# final_project.net
KiCad netlist of a schematic drawn in Altium Designer
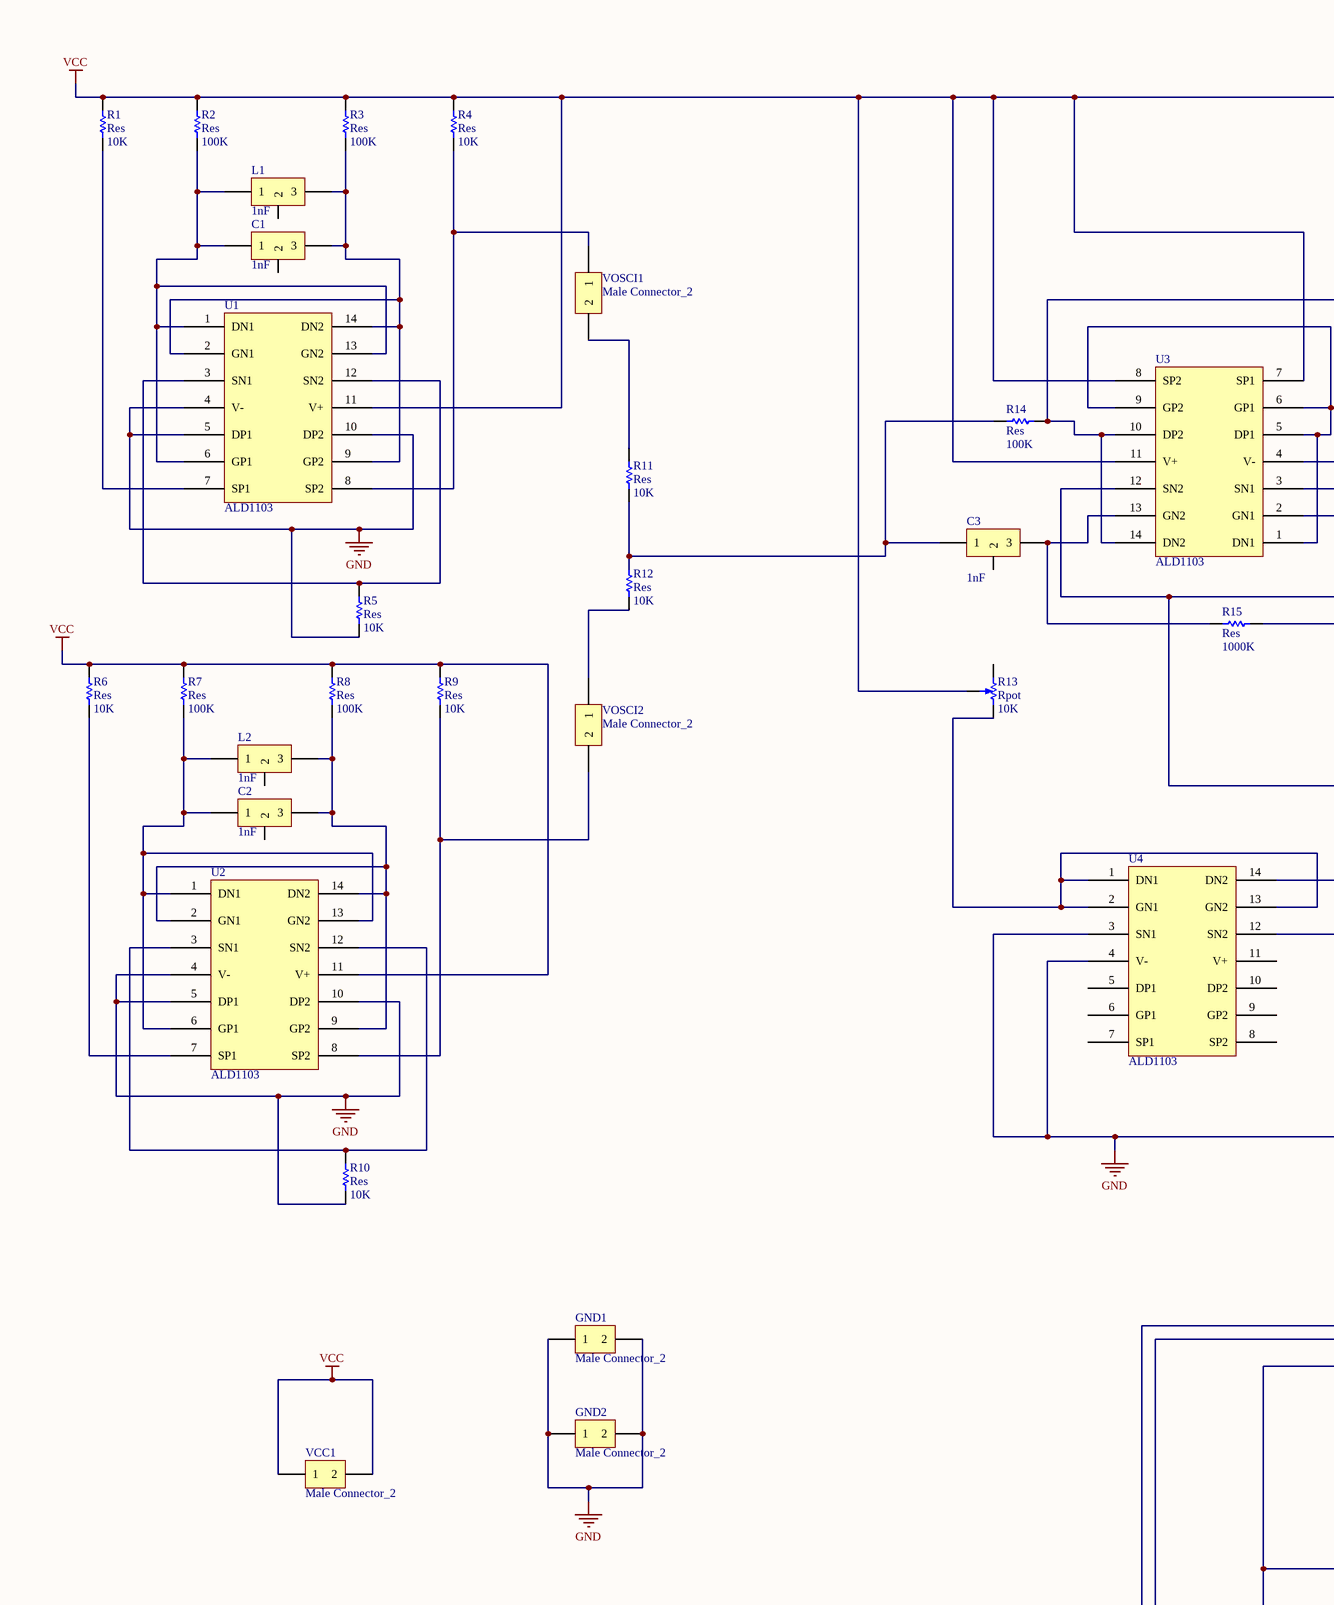
[diagram p0: final_project.SchDoc, left]
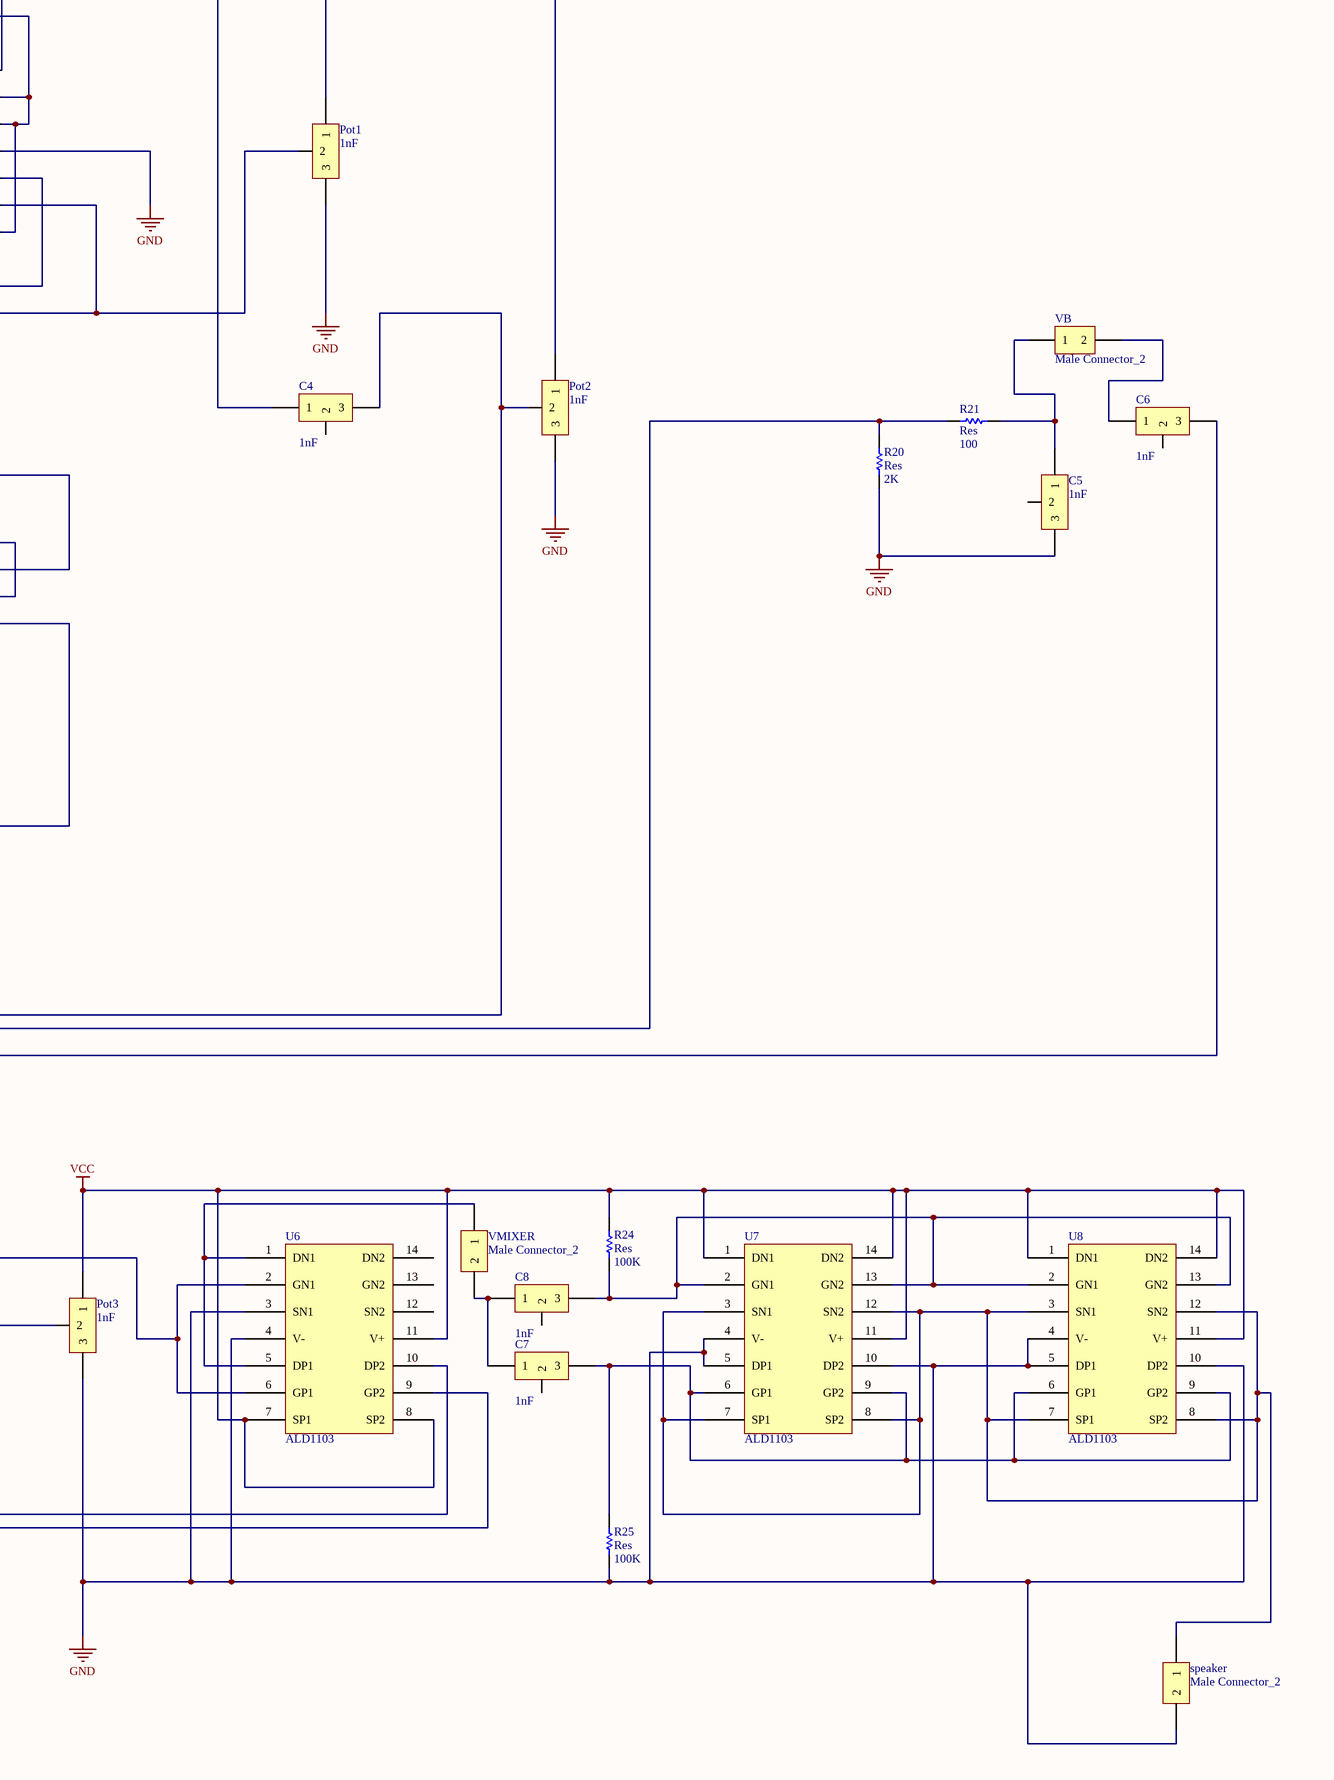
[diagram p1: final_project.SchDoc, right]

(export (version "E")
  (design (tool "Eeschema 10.0.6"))
  (components
    (comp (ref "C1")
      (value "1nF")
      (footprint "Connector_3")
      (fields (field (name "Comment") "Female Connector_3"))
      (libsource (lib "ESE319_Components") (part "Female Connector_3"))
    )
    (comp (ref "C2")
      (value "1nF")
      (footprint "Connector_3")
      (fields (field (name "Comment") "Female Connector_3"))
      (libsource (lib "ESE319_Components") (part "Female Connector_3"))
    )
    (comp (ref "C3")
      (value "1nF")
      (footprint "Connector_3")
      (fields (field (name "Comment") "Female Connector_3"))
      (libsource (lib "ESE319_Components") (part "Female Connector_3"))
    )
    (comp (ref "C4")
      (value "1nF")
      (footprint "Connector_3")
      (fields (field (name "Comment") "Female Connector_3"))
      (libsource (lib "ESE319_Components") (part "Female Connector_3"))
    )
    (comp (ref "C5")
      (value "1nF")
      (footprint "Connector_3")
      (fields (field (name "Comment") "Female Connector_3"))
      (libsource (lib "") (part "Female Connector_3_1"))
    )
    (comp (ref "C6")
      (value "1nF")
      (footprint "Connector_3")
      (fields (field (name "Comment") "Female Connector_3"))
      (libsource (lib "ESE319_Components") (part "Female Connector_3"))
    )
    (comp (ref "C7")
      (value "1nF")
      (footprint "Connector_3")
      (fields (field (name "Comment") "Female Connector_3"))
      (libsource (lib "ESE319_Components") (part "Female Connector_3"))
    )
    (comp (ref "C8")
      (value "1nF")
      (footprint "Connector_3")
      (fields (field (name "Comment") "Female Connector_3"))
      (libsource (lib "ESE319_Components") (part "Female Connector_3"))
    )
    (comp (ref "GND1")
      (value "Male Connector_2")
      (footprint "Connector_2")
      (libsource (lib "ESE319_Components") (part "Male Connector_2"))
    )
    (comp (ref "GND2")
      (value "Male Connector_2")
      (footprint "Connector_2")
      (libsource (lib "ESE319_Components") (part "Male Connector_2"))
    )
    (comp (ref "L1")
      (value "1nF")
      (footprint "Connector_3")
      (fields (field (name "Comment") "Female Connector_3"))
      (libsource (lib "ESE319_Components") (part "Female Connector_3"))
    )
    (comp (ref "L2")
      (value "1nF")
      (footprint "Connector_3")
      (fields (field (name "Comment") "Female Connector_3"))
      (libsource (lib "ESE319_Components") (part "Female Connector_3"))
    )
    (comp (ref "Pot1")
      (value "1nF")
      (footprint "Connector_3")
      (fields (field (name "Comment") "Female Connector_3"))
      (libsource (lib "") (part "Female Connector_3_1"))
    )
    (comp (ref "Pot2")
      (value "1nF")
      (footprint "Connector_3")
      (fields (field (name "Comment") "Female Connector_3"))
      (libsource (lib "") (part "Female Connector_3_1"))
    )
    (comp (ref "Pot3")
      (value "1nF")
      (footprint "Connector_3")
      (fields (field (name "Comment") "Female Connector_3"))
      (libsource (lib "") (part "Female Connector_3_1"))
    )
    (comp (ref "R1")
      (value "Res")
      (footprint "RES")
      (fields (field (name "ALTIUM_VALUE") "10K"))
      (libsource (lib "ESE319_Components") (part "Resistor"))
    )
    (comp (ref "R2")
      (value "Res")
      (footprint "RES")
      (fields (field (name "ALTIUM_VALUE") "100K"))
      (libsource (lib "ESE319_Components") (part "Resistor"))
    )
    (comp (ref "R3")
      (value "Res")
      (footprint "RES")
      (fields (field (name "ALTIUM_VALUE") "100K"))
      (libsource (lib "ESE319_Components") (part "Resistor"))
    )
    (comp (ref "R4")
      (value "Res")
      (footprint "RES")
      (fields (field (name "ALTIUM_VALUE") "10K"))
      (libsource (lib "ESE319_Components") (part "Resistor"))
    )
    (comp (ref "R5")
      (value "Res")
      (footprint "RES")
      (fields (field (name "ALTIUM_VALUE") "10K"))
      (libsource (lib "ESE319_Components") (part "Resistor"))
    )
    (comp (ref "R6")
      (value "Res")
      (footprint "RES")
      (fields (field (name "ALTIUM_VALUE") "10K"))
      (libsource (lib "ESE319_Components") (part "Resistor"))
    )
    (comp (ref "R7")
      (value "Res")
      (footprint "RES")
      (fields (field (name "ALTIUM_VALUE") "100K"))
      (libsource (lib "ESE319_Components") (part "Resistor"))
    )
    (comp (ref "R8")
      (value "Res")
      (footprint "RES")
      (fields (field (name "ALTIUM_VALUE") "100K"))
      (libsource (lib "ESE319_Components") (part "Resistor"))
    )
    (comp (ref "R9")
      (value "Res")
      (footprint "RES")
      (fields (field (name "ALTIUM_VALUE") "10K"))
      (libsource (lib "ESE319_Components") (part "Resistor"))
    )
    (comp (ref "R10")
      (value "Res")
      (footprint "RES")
      (fields (field (name "ALTIUM_VALUE") "10K"))
      (libsource (lib "ESE319_Components") (part "Resistor"))
    )
    (comp (ref "R11")
      (value "Res")
      (footprint "RES")
      (fields (field (name "ALTIUM_VALUE") "10K"))
      (libsource (lib "ESE319_Components") (part "Resistor"))
    )
    (comp (ref "R12")
      (value "Res")
      (footprint "RES")
      (fields (field (name "ALTIUM_VALUE") "10K"))
      (libsource (lib "ESE319_Components") (part "Resistor"))
    )
    (comp (ref "R13")
      (value "Rpot")
      (footprint "Rpot10")
      (fields (field (name "ALTIUM_VALUE") "10K"))
      (libsource (lib "ESE319_Components") (part "Rpot_10K"))
    )
    (comp (ref "R14")
      (value "Res")
      (footprint "RES")
      (fields (field (name "ALTIUM_VALUE") "100K"))
      (libsource (lib "ESE319_Components") (part "Resistor"))
    )
    (comp (ref "R15")
      (value "Res")
      (footprint "RES")
      (fields (field (name "ALTIUM_VALUE") "1000K"))
      (libsource (lib "ESE319_Components") (part "Resistor"))
    )
    (comp (ref "R20")
      (value "Res")
      (footprint "RES")
      (fields (field (name "ALTIUM_VALUE") "2K"))
      (libsource (lib "ESE319_Components") (part "Resistor"))
    )
    (comp (ref "R21")
      (value "Res")
      (footprint "RES")
      (fields (field (name "ALTIUM_VALUE") "100"))
      (libsource (lib "ESE319_Components") (part "Resistor"))
    )
    (comp (ref "R24")
      (value "Res")
      (footprint "RES")
      (fields (field (name "ALTIUM_VALUE") "100K"))
      (libsource (lib "ESE319_Components") (part "Resistor"))
    )
    (comp (ref "R25")
      (value "Res")
      (footprint "RES")
      (fields (field (name "ALTIUM_VALUE") "100K"))
      (libsource (lib "ESE319_Components") (part "Resistor"))
    )
    (comp (ref "speaker")
      (value "Male Connector_2")
      (footprint "Connector_2")
      (libsource (lib "") (part "Male Connector_2_1"))
    )
    (comp (ref "U1")
      (value "ALD1103")
      (footprint "ALD1103")
      (libsource (lib "ESE319_Components") (part "ALD1103"))
    )
    (comp (ref "U2")
      (value "ALD1103")
      (footprint "ALD1103")
      (libsource (lib "ESE319_Components") (part "ALD1103"))
    )
    (comp (ref "U3") (value "ALD1103") (footprint "ALD1103") (libsource (lib "") (part "ALD1103_1")))
    (comp (ref "U4")
      (value "ALD1103")
      (footprint "ALD1103")
      (libsource (lib "ESE319_Components") (part "ALD1103"))
    )
    (comp (ref "U6")
      (value "ALD1103")
      (footprint "ALD1103")
      (libsource (lib "ESE319_Components") (part "ALD1103"))
    )
    (comp (ref "U7")
      (value "ALD1103")
      (footprint "ALD1103")
      (libsource (lib "ESE319_Components") (part "ALD1103"))
    )
    (comp (ref "U8")
      (value "ALD1103")
      (footprint "ALD1103")
      (libsource (lib "ESE319_Components") (part "ALD1103"))
    )
    (comp (ref "VB")
      (value "Male Connector_2")
      (footprint "Connector_2")
      (libsource (lib "ESE319_Components") (part "Male Connector_2"))
    )
    (comp (ref "VCC1")
      (value "Male Connector_2")
      (footprint "Connector_2")
      (libsource (lib "ESE319_Components") (part "Male Connector_2"))
    )
    (comp (ref "VMIXER")
      (value "Male Connector_2")
      (footprint "Connector_2")
      (libsource (lib "") (part "Male Connector_2_1"))
    )
    (comp (ref "VOSCI1")
      (value "Male Connector_2")
      (footprint "Connector_2")
      (libsource (lib "") (part "Male Connector_2_1"))
    )
    (comp (ref "VOSCI2")
      (value "Male Connector_2")
      (footprint "Connector_2")
      (libsource (lib "") (part "Male Connector_2_1"))
    )
  )
  (nets
    (net (code "1") (name "GND") (class "Default")
      (node (ref "C5") (pin "3") (pinfunction "3_3") (pintype "passive"))
      (node (ref "GND1") (pin "1") (pinfunction "1_1") (pintype "passive"))
      (node (ref "GND1") (pin "2") (pinfunction "2_2") (pintype "passive"))
      (node (ref "GND2") (pin "1") (pinfunction "1_1") (pintype "passive"))
      (node (ref "GND2") (pin "2") (pinfunction "2_2") (pintype "passive"))
      (node (ref "Pot1") (pin "3") (pinfunction "3_3") (pintype "passive"))
      (node (ref "Pot2") (pin "3") (pinfunction "3_3") (pintype "passive"))
      (node (ref "Pot3") (pin "3") (pinfunction "3_3") (pintype "passive"))
      (node (ref "R10") (pin "1") (pinfunction "1_1") (pintype "passive"))
      (node (ref "R20") (pin "1") (pinfunction "1_1") (pintype "passive"))
      (node (ref "R25") (pin "1") (pinfunction "1_1") (pintype "passive"))
      (node (ref "R5") (pin "1") (pinfunction "1_1") (pintype "passive"))
      (node (ref "U1") (pin "10") (pinfunction "DP2_10") (pintype "passive"))
      (node (ref "U1") (pin "4") (pinfunction "V-_4") (pintype "passive"))
      (node (ref "U1") (pin "5") (pinfunction "DP1_5") (pintype "passive"))
      (node (ref "U2") (pin "10") (pinfunction "DP2_10") (pintype "passive"))
      (node (ref "U2") (pin "4") (pinfunction "V-_4") (pintype "passive"))
      (node (ref "U2") (pin "5") (pinfunction "DP1_5") (pintype "passive"))
      (node (ref "U3") (pin "4") (pinfunction "V-_4") (pintype "passive"))
      (node (ref "U4") (pin "12") (pinfunction "SN2_12") (pintype "passive"))
      (node (ref "U4") (pin "3") (pinfunction "SN1_3") (pintype "passive"))
      (node (ref "U4") (pin "4") (pinfunction "V-_4") (pintype "passive"))
      (node (ref "U6") (pin "3") (pinfunction "SN1_3") (pintype "passive"))
      (node (ref "U6") (pin "4") (pinfunction "V-_4") (pintype "passive"))
      (node (ref "U7") (pin "10") (pinfunction "DP2_10") (pintype "passive"))
      (node (ref "U7") (pin "4") (pinfunction "V-_4") (pintype "passive"))
      (node (ref "U7") (pin "5") (pinfunction "DP1_5") (pintype "passive"))
      (node (ref "U8") (pin "10") (pinfunction "DP2_10") (pintype "passive"))
      (node (ref "U8") (pin "4") (pinfunction "V-_4") (pintype "passive"))
      (node (ref "U8") (pin "5") (pinfunction "DP1_5") (pintype "passive"))
      (node (ref "speaker") (pin "2") (pinfunction "2_2") (pintype "passive"))
    )
    (net (code "2") (name "Net-(C3-Pad1)") (class "Default")
      (node (ref "C3") (pin "1") (pinfunction "1_1") (pintype "passive"))
      (node (ref "R11") (pin "1") (pinfunction "1_1") (pintype "passive"))
      (node (ref "R12") (pin "2") (pinfunction "2_2") (pintype "passive"))
      (node (ref "R14") (pin "1") (pinfunction "1_1") (pintype "passive"))
    )
    (net (code "3") (name "Net-(C5-Pad1)") (class "Default")
      (node (ref "C5") (pin "1") (pinfunction "1_1") (pintype "passive"))
      (node (ref "R21") (pin "1") (pinfunction "1_1") (pintype "passive"))
      (node (ref "VB") (pin "1") (pinfunction "1_1") (pintype "passive"))
    )
    (net (code "4") (name "Net-(C6-Pad1)") (class "Default")
      (node (ref "C6") (pin "1") (pinfunction "1_1") (pintype "passive"))
      (node (ref "VB") (pin "2") (pinfunction "2_2") (pintype "passive"))
    )
    (net (code "5") (name "Net-(C7-Pad1)") (class "Default")
      (node (ref "C7") (pin "1") (pinfunction "1_1") (pintype "passive"))
      (node (ref "C8") (pin "1") (pinfunction "1_1") (pintype "passive"))
      (node (ref "VMIXER") (pin "2") (pinfunction "2_2") (pintype "passive"))
    )
    (net (code "6") (name "Net-(R11-Pad2)") (class "Default")
      (node (ref "R11") (pin "2") (pinfunction "2_2") (pintype "passive"))
      (node (ref "VOSCI1") (pin "2") (pinfunction "2_2") (pintype "passive"))
    )
    (net (code "7") (name "Net-(R12-Pad1)") (class "Default")
      (node (ref "R12") (pin "1") (pinfunction "1_1") (pintype "passive"))
      (node (ref "VOSCI2") (pin "1") (pinfunction "1_1") (pintype "passive"))
    )
    (net (code "8") (name "Net-(U1-DN1)") (class "Default")
      (node (ref "C1") (pin "1") (pinfunction "1_1") (pintype "passive"))
      (node (ref "L1") (pin "1") (pinfunction "1_1") (pintype "passive"))
      (node (ref "R2") (pin "1") (pinfunction "1_1") (pintype "passive"))
      (node (ref "U1") (pin "1") (pinfunction "DN1_1") (pintype "passive"))
      (node (ref "U1") (pin "13") (pinfunction "GN2_13") (pintype "passive"))
      (node (ref "U1") (pin "6") (pinfunction "GP1_6") (pintype "passive"))
    )
    (net (code "9") (name "Net-(U1-DN2)") (class "Default")
      (node (ref "C1") (pin "3") (pinfunction "3_3") (pintype "passive"))
      (node (ref "L1") (pin "3") (pinfunction "3_3") (pintype "passive"))
      (node (ref "R3") (pin "1") (pinfunction "1_1") (pintype "passive"))
      (node (ref "U1") (pin "14") (pinfunction "DN2_14") (pintype "passive"))
      (node (ref "U1") (pin "2") (pinfunction "GN1_2") (pintype "passive"))
      (node (ref "U1") (pin "9") (pinfunction "GP2_9") (pintype "passive"))
    )
    (net (code "10") (name "Net-(U1-SN1)") (class "Default")
      (node (ref "R5") (pin "2") (pinfunction "2_2") (pintype "passive"))
      (node (ref "U1") (pin "12") (pinfunction "SN2_12") (pintype "passive"))
      (node (ref "U1") (pin "3") (pinfunction "SN1_3") (pintype "passive"))
    )
    (net (code "11") (name "Net-(U1-SP1)") (class "Default")
      (node (ref "R1") (pin "1") (pinfunction "1_1") (pintype "passive"))
      (node (ref "U1") (pin "7") (pinfunction "SP1_7") (pintype "passive"))
    )
    (net (code "12") (name "Net-(U1-SP2)") (class "Default")
      (node (ref "R4") (pin "1") (pinfunction "1_1") (pintype "passive"))
      (node (ref "U1") (pin "8") (pinfunction "SP2_8") (pintype "passive"))
      (node (ref "VOSCI1") (pin "1") (pinfunction "1_1") (pintype "passive"))
    )
    (net (code "13") (name "Net-(U2-DN1)") (class "Default")
      (node (ref "C2") (pin "1") (pinfunction "1_1") (pintype "passive"))
      (node (ref "L2") (pin "1") (pinfunction "1_1") (pintype "passive"))
      (node (ref "R7") (pin "1") (pinfunction "1_1") (pintype "passive"))
      (node (ref "U2") (pin "1") (pinfunction "DN1_1") (pintype "passive"))
      (node (ref "U2") (pin "13") (pinfunction "GN2_13") (pintype "passive"))
      (node (ref "U2") (pin "6") (pinfunction "GP1_6") (pintype "passive"))
    )
    (net (code "14") (name "Net-(U2-DN2)") (class "Default")
      (node (ref "C2") (pin "3") (pinfunction "3_3") (pintype "passive"))
      (node (ref "L2") (pin "3") (pinfunction "3_3") (pintype "passive"))
      (node (ref "R8") (pin "1") (pinfunction "1_1") (pintype "passive"))
      (node (ref "U2") (pin "14") (pinfunction "DN2_14") (pintype "passive"))
      (node (ref "U2") (pin "2") (pinfunction "GN1_2") (pintype "passive"))
      (node (ref "U2") (pin "9") (pinfunction "GP2_9") (pintype "passive"))
    )
    (net (code "15") (name "Net-(U2-SN1)") (class "Default")
      (node (ref "R10") (pin "2") (pinfunction "2_2") (pintype "passive"))
      (node (ref "U2") (pin "12") (pinfunction "SN2_12") (pintype "passive"))
      (node (ref "U2") (pin "3") (pinfunction "SN1_3") (pintype "passive"))
    )
    (net (code "16") (name "Net-(U2-SP1)") (class "Default")
      (node (ref "R6") (pin "1") (pinfunction "1_1") (pintype "passive"))
      (node (ref "U2") (pin "7") (pinfunction "SP1_7") (pintype "passive"))
    )
    (net (code "17") (name "Net-(U2-SP2)") (class "Default")
      (node (ref "R9") (pin "1") (pinfunction "1_1") (pintype "passive"))
      (node (ref "U2") (pin "8") (pinfunction "SP2_8") (pintype "passive"))
      (node (ref "VOSCI2") (pin "2") (pinfunction "2_2") (pintype "passive"))
    )
    (net (code "18") (name "Net-(U3-DN1)") (class "Default")
      (node (ref "U3") (pin "1") (pinfunction "DN1_1") (pintype "passive"))
      (node (ref "U3") (pin "5") (pinfunction "DP1_5") (pintype "passive"))
      (node (ref "U3") (pin "6") (pinfunction "GP1_6") (pintype "passive"))
      (node (ref "U3") (pin "9") (pinfunction "GP2_9") (pintype "passive"))
    )
    (net (code "19") (name "Net-(U3-DN2)") (class "Default")
      (node (ref "C4") (pin "1") (pinfunction "1_1") (pintype "passive"))
      (node (ref "R14") (pin "2") (pinfunction "2_2") (pintype "passive"))
      (node (ref "U3") (pin "10") (pinfunction "DP2_10") (pintype "passive"))
      (node (ref "U3") (pin "14") (pinfunction "DN2_14") (pintype "passive"))
    )
    (net (code "20") (name "Net-(U3-GN1)") (class "Default")
      (node (ref "Pot1") (pin "2") (pinfunction "2_2") (pintype "passive"))
      (node (ref "R15") (pin "1") (pinfunction "1_1") (pintype "passive"))
      (node (ref "U3") (pin "2") (pinfunction "GN1_2") (pintype "passive"))
    )
    (net (code "21") (name "Net-(U3-GN2)") (class "Default")
      (node (ref "C3") (pin "3") (pinfunction "3_3") (pintype "passive"))
      (node (ref "R15") (pin "2") (pinfunction "2_2") (pintype "passive"))
      (node (ref "U3") (pin "13") (pinfunction "GN2_13") (pintype "passive"))
    )
    (net (code "22") (name "Net-(U3-SN1)") (class "Default")
      (node (ref "U3") (pin "12") (pinfunction "SN2_12") (pintype "passive"))
      (node (ref "U3") (pin "3") (pinfunction "SN1_3") (pintype "passive"))
      (node (ref "U4") (pin "14") (pinfunction "DN2_14") (pintype "passive"))
    )
    (net (code "23") (name "Net-(U4-DN1)") (class "Default")
      (node (ref "R13") (pin "2") (pintype "passive"))
      (node (ref "U4") (pin "1") (pinfunction "DN1_1") (pintype "passive"))
      (node (ref "U4") (pin "13") (pinfunction "GN2_13") (pintype "passive"))
      (node (ref "U4") (pin "2") (pinfunction "GN1_2") (pintype "passive"))
    )
    (net (code "24") (name "Net-(U6-DN1)") (class "Default")
      (node (ref "U6") (pin "1") (pinfunction "DN1_1") (pintype "passive"))
      (node (ref "U6") (pin "5") (pinfunction "DP1_5") (pintype "passive"))
      (node (ref "VMIXER") (pin "1") (pinfunction "1_1") (pintype "passive"))
    )
    (net (code "25") (name "Net-(U6-DP2)") (class "Default")
      (node (ref "R20") (pin "2") (pinfunction "2_2") (pintype "passive"))
      (node (ref "R21") (pin "2") (pinfunction "2_2") (pintype "passive"))
      (node (ref "U6") (pin "10") (pinfunction "DP2_10") (pintype "passive"))
    )
    (net (code "26") (name "Net-(U6-GN1)") (class "Default")
      (node (ref "C6") (pin "3") (pinfunction "3_3") (pintype "passive"))
      (node (ref "Pot3") (pin "2") (pinfunction "2_2") (pintype "passive"))
      (node (ref "U6") (pin "2") (pinfunction "GN1_2") (pintype "passive"))
      (node (ref "U6") (pin "6") (pinfunction "GP1_6") (pintype "passive"))
    )
    (net (code "27") (name "Net-(U6-GP2)") (class "Default")
      (node (ref "C4") (pin "3") (pinfunction "3_3") (pintype "passive"))
      (node (ref "Pot2") (pin "2") (pinfunction "2_2") (pintype "passive"))
      (node (ref "U6") (pin "9") (pinfunction "GP2_9") (pintype "passive"))
    )
    (net (code "28") (name "Net-(U7-GN1)") (class "Default")
      (node (ref "C8") (pin "3") (pinfunction "3_3") (pintype "passive"))
      (node (ref "R24") (pin "1") (pinfunction "1_1") (pintype "passive"))
      (node (ref "U7") (pin "13") (pinfunction "GN2_13") (pintype "passive"))
      (node (ref "U7") (pin "2") (pinfunction "GN1_2") (pintype "passive"))
      (node (ref "U8") (pin "13") (pinfunction "GN2_13") (pintype "passive"))
      (node (ref "U8") (pin "2") (pinfunction "GN1_2") (pintype "passive"))
    )
    (net (code "29") (name "Net-(U7-GP1)") (class "Default")
      (node (ref "C7") (pin "3") (pinfunction "3_3") (pintype "passive"))
      (node (ref "R25") (pin "2") (pinfunction "2_2") (pintype "passive"))
      (node (ref "U7") (pin "6") (pinfunction "GP1_6") (pintype "passive"))
      (node (ref "U7") (pin "9") (pinfunction "GP2_9") (pintype "passive"))
      (node (ref "U8") (pin "6") (pinfunction "GP1_6") (pintype "passive"))
      (node (ref "U8") (pin "9") (pinfunction "GP2_9") (pintype "passive"))
    )
    (net (code "30") (name "Net-(U7-SN1)") (class "Default")
      (node (ref "U7") (pin "12") (pinfunction "SN2_12") (pintype "passive"))
      (node (ref "U7") (pin "3") (pinfunction "SN1_3") (pintype "passive"))
      (node (ref "U7") (pin "7") (pinfunction "SP1_7") (pintype "passive"))
      (node (ref "U7") (pin "8") (pinfunction "SP2_8") (pintype "passive"))
      (node (ref "U8") (pin "12") (pinfunction "SN2_12") (pintype "passive"))
      (node (ref "U8") (pin "3") (pinfunction "SN1_3") (pintype "passive"))
      (node (ref "U8") (pin "7") (pinfunction "SP1_7") (pintype "passive"))
      (node (ref "U8") (pin "8") (pinfunction "SP2_8") (pintype "passive"))
      (node (ref "speaker") (pin "1") (pinfunction "1_1") (pintype "passive"))
    )
    (net (code "31") (name "VCC") (class "Default")
      (node (ref "Pot1") (pin "1") (pinfunction "1_1") (pintype "passive"))
      (node (ref "Pot2") (pin "1") (pinfunction "1_1") (pintype "passive"))
      (node (ref "Pot3") (pin "1") (pinfunction "1_1") (pintype "passive"))
      (node (ref "R1") (pin "2") (pinfunction "2_2") (pintype "passive"))
      (node (ref "R13") (pin "3") (pintype "passive"))
      (node (ref "R2") (pin "2") (pinfunction "2_2") (pintype "passive"))
      (node (ref "R24") (pin "2") (pinfunction "2_2") (pintype "passive"))
      (node (ref "R3") (pin "2") (pinfunction "2_2") (pintype "passive"))
      (node (ref "R4") (pin "2") (pinfunction "2_2") (pintype "passive"))
      (node (ref "R6") (pin "2") (pinfunction "2_2") (pintype "passive"))
      (node (ref "R7") (pin "2") (pinfunction "2_2") (pintype "passive"))
      (node (ref "R8") (pin "2") (pinfunction "2_2") (pintype "passive"))
      (node (ref "R9") (pin "2") (pinfunction "2_2") (pintype "passive"))
      (node (ref "U1") (pin "11") (pinfunction "V+_11") (pintype "passive"))
      (node (ref "U2") (pin "11") (pinfunction "V+_11") (pintype "passive"))
      (node (ref "U3") (pin "11") (pinfunction "V+_11") (pintype "passive"))
      (node (ref "U3") (pin "7") (pinfunction "SP1_7") (pintype "passive"))
      (node (ref "U3") (pin "8") (pinfunction "SP2_8") (pintype "passive"))
      (node (ref "U6") (pin "11") (pinfunction "V+_11") (pintype "passive"))
      (node (ref "U6") (pin "7") (pinfunction "SP1_7") (pintype "passive"))
      (node (ref "U6") (pin "8") (pinfunction "SP2_8") (pintype "passive"))
      (node (ref "U7") (pin "1") (pinfunction "DN1_1") (pintype "passive"))
      (node (ref "U7") (pin "11") (pinfunction "V+_11") (pintype "passive"))
      (node (ref "U7") (pin "14") (pinfunction "DN2_14") (pintype "passive"))
      (node (ref "U8") (pin "1") (pinfunction "DN1_1") (pintype "passive"))
      (node (ref "U8") (pin "11") (pinfunction "V+_11") (pintype "passive"))
      (node (ref "U8") (pin "14") (pinfunction "DN2_14") (pintype "passive"))
      (node (ref "VCC1") (pin "1") (pinfunction "1_1") (pintype "passive"))
      (node (ref "VCC1") (pin "2") (pinfunction "2_2") (pintype "passive"))
    )
    (net (code "32") (name "unconnected-(C1-Pad2)") (class "Default")
      (node (ref "C1") (pin "2") (pinfunction "2_2") (pintype "passive"))
    )
    (net (code "33") (name "unconnected-(C2-Pad2)") (class "Default")
      (node (ref "C2") (pin "2") (pinfunction "2_2") (pintype "passive"))
    )
    (net (code "34") (name "unconnected-(C3-Pad2)") (class "Default")
      (node (ref "C3") (pin "2") (pinfunction "2_2") (pintype "passive"))
    )
    (net (code "35") (name "unconnected-(C4-Pad2)") (class "Default")
      (node (ref "C4") (pin "2") (pinfunction "2_2") (pintype "passive"))
    )
    (net (code "36") (name "unconnected-(C5-Pad2)") (class "Default")
      (node (ref "C5") (pin "2") (pinfunction "2_2") (pintype "passive"))
    )
    (net (code "37") (name "unconnected-(C6-Pad2)") (class "Default")
      (node (ref "C6") (pin "2") (pinfunction "2_2") (pintype "passive"))
    )
    (net (code "38") (name "unconnected-(C7-Pad2)") (class "Default")
      (node (ref "C7") (pin "2") (pinfunction "2_2") (pintype "passive"))
    )
    (net (code "39") (name "unconnected-(C8-Pad2)") (class "Default")
      (node (ref "C8") (pin "2") (pinfunction "2_2") (pintype "passive"))
    )
    (net (code "40") (name "unconnected-(L1-Pad2)") (class "Default")
      (node (ref "L1") (pin "2") (pinfunction "2_2") (pintype "passive"))
    )
    (net (code "41") (name "unconnected-(L2-Pad2)") (class "Default")
      (node (ref "L2") (pin "2") (pinfunction "2_2") (pintype "passive"))
    )
    (net (code "42") (name "unconnected-(R13---Pad1)") (class "Default")
      (node (ref "R13") (pin "1") (pinfunction "-_1") (pintype "passive"))
    )
    (net (code "43") (name "unconnected-(U4-DP1-Pad5)") (class "Default")
      (node (ref "U4") (pin "5") (pinfunction "DP1_5") (pintype "passive"))
    )
    (net (code "44") (name "unconnected-(U4-DP2-Pad10)") (class "Default")
      (node (ref "U4") (pin "10") (pinfunction "DP2_10") (pintype "passive"))
    )
    (net (code "45") (name "unconnected-(U4-GP1-Pad6)") (class "Default")
      (node (ref "U4") (pin "6") (pinfunction "GP1_6") (pintype "passive"))
    )
    (net (code "46") (name "unconnected-(U4-GP2-Pad9)") (class "Default")
      (node (ref "U4") (pin "9") (pinfunction "GP2_9") (pintype "passive"))
    )
    (net (code "47") (name "unconnected-(U4-SP1-Pad7)") (class "Default")
      (node (ref "U4") (pin "7") (pinfunction "SP1_7") (pintype "passive"))
    )
    (net (code "48") (name "unconnected-(U4-SP2-Pad8)") (class "Default")
      (node (ref "U4") (pin "8") (pinfunction "SP2_8") (pintype "passive"))
    )
    (net (code "49") (name "unconnected-(U4-V+-Pad11)") (class "Default")
      (node (ref "U4") (pin "11") (pinfunction "V+_11") (pintype "passive"))
    )
    (net (code "50") (name "unconnected-(U6-DN2-Pad14)") (class "Default")
      (node (ref "U6") (pin "14") (pinfunction "DN2_14") (pintype "passive"))
    )
    (net (code "51") (name "unconnected-(U6-GN2-Pad13)") (class "Default")
      (node (ref "U6") (pin "13") (pinfunction "GN2_13") (pintype "passive"))
    )
    (net (code "52") (name "unconnected-(U6-SN2-Pad12)") (class "Default")
      (node (ref "U6") (pin "12") (pinfunction "SN2_12") (pintype "passive"))
    )
  )
)
